# compass.net
KiCad netlist of a schematic drawn in EAGLE
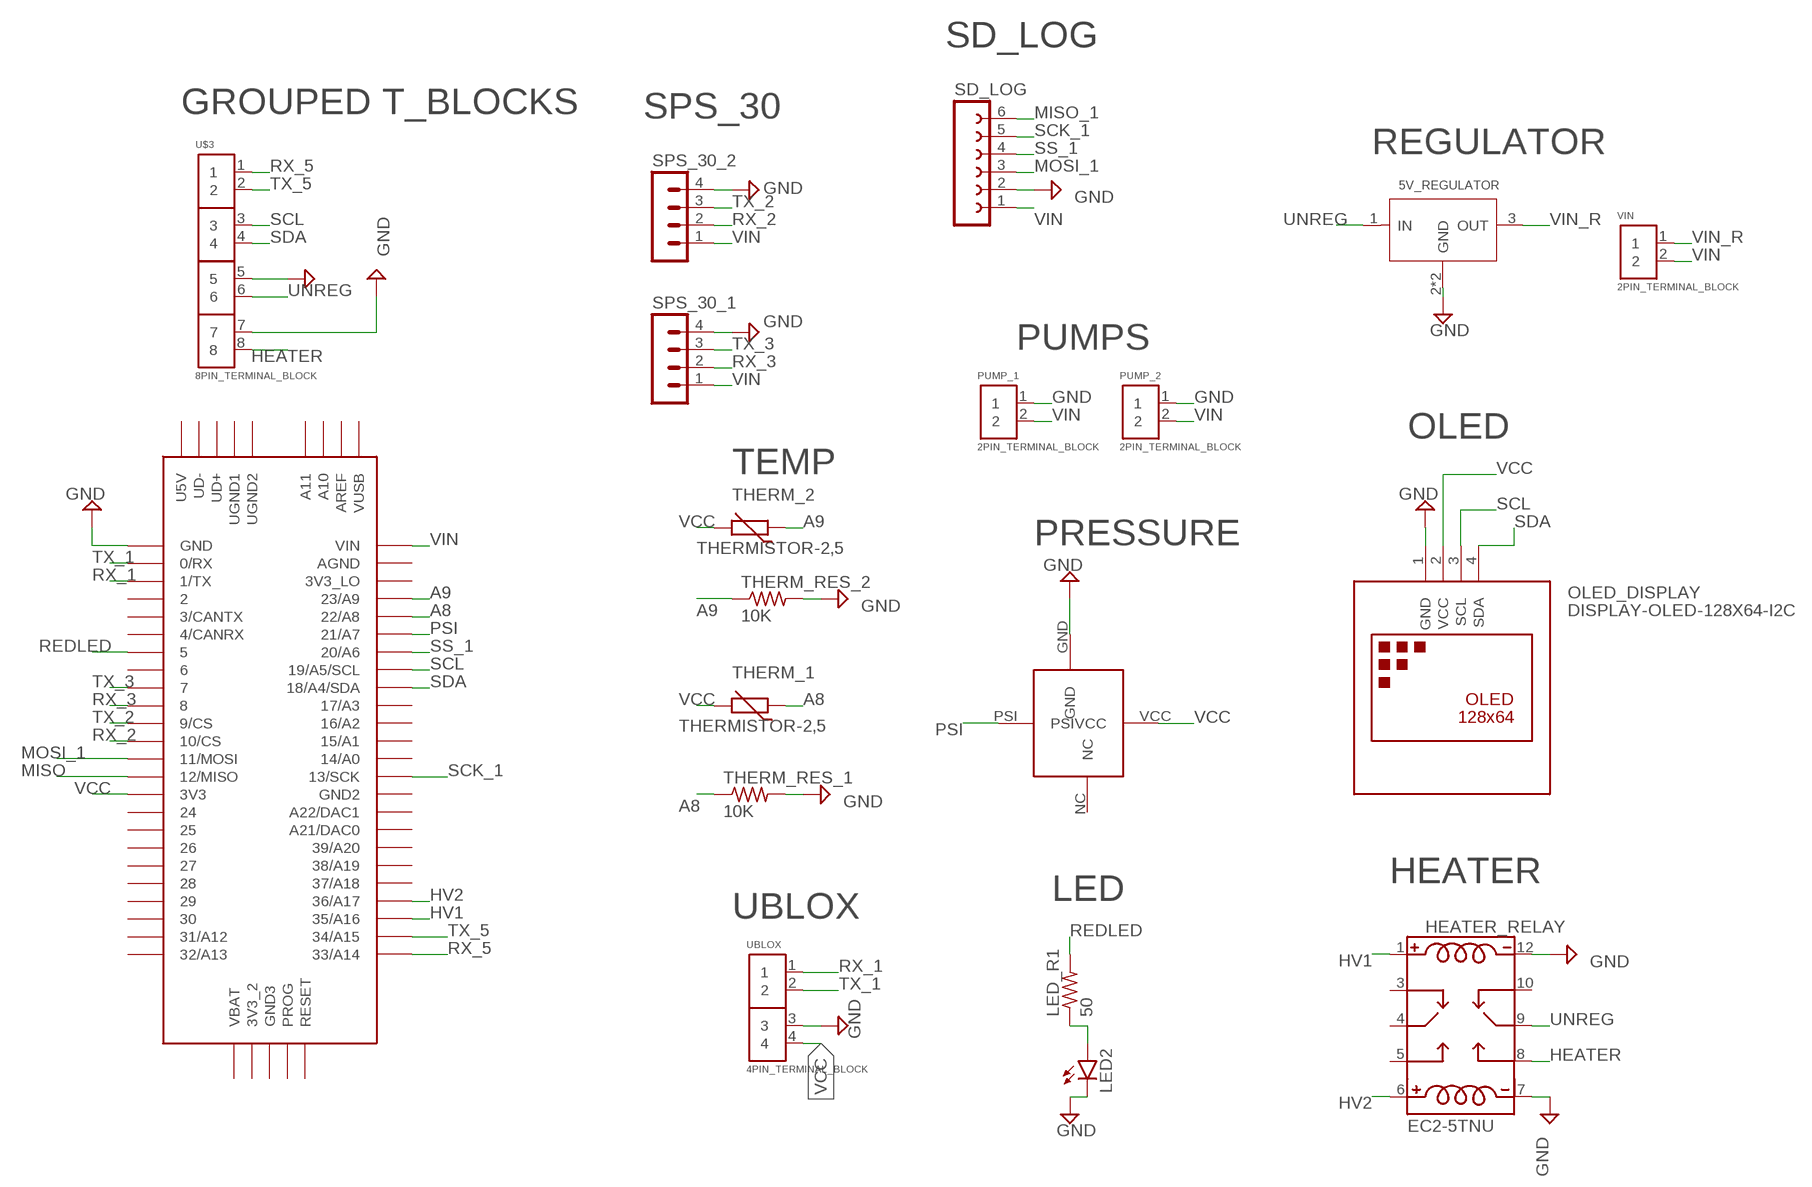
[diagram p0: schematic, sheet 1]

(export (version "E")
  (design (tool "Eeschema 10.0.6"))
  (components
    (comp (ref "5V_REGULATOR")
      (value "PMIC-L7805CV-DG(TO-220)")
      (footprint "eagle-import:TO-220")
      (fields
        (field (name "DIGI-KEY_PART_NUMBER") "497-12404-ND")
        (field (name "MF") "STMicroelectronics")
        (field (name "MP") "L7805CV-DG")
      )
      (libsource (lib "eagle-import") (part "PMIC-L7805CV-DG(TO-220)"))
    )
    (comp (ref "HEATER_RELAY")
      (value "EC2-5TNU")
      (footprint "eagle-import:RELAY_EC2-5TNU")
      (fields (field (name "MF") "KEMET"))
      (libsource (lib "eagle-import") (part "EC2-5TNU"))
    )
    (comp (ref "LED2")
      (value "TLLR4400")
      (footprint "eagle-import:LED3MM")
      (fields (field (name "MF") "VISHAY SEMICONDUCTOR"))
      (libsource (lib "eagle-import") (part "TLLR4400"))
    )
    (comp (ref "LED_R1")
      (value "50")
      (footprint "eagle-import:0204_7")
      (libsource (lib "eagle-import") (part "resistor_348_R-US_0204/7"))
    )
    (comp (ref "OLED_DISPLAY")
      (value "DISPLAY-OLED-128X64-I2C")
      (footprint "eagle-import:DISPLAY-OLED-128X64-I2C")
      (libsource (lib "eagle-import") (part "DISPLAY-OLED-128X64-I2C"))
    )
    (comp (ref "PRESSURE_SENSOR")
      (value "SSCSANN015PAAA5")
      (footprint "eagle-import:SSCSANN015PAAA5")
      (libsource (lib "eagle-import") (part "SSCSANN015PAAA5"))
    )
    (comp (ref "PUMP_1")
      (value "2PIN_TERMINAL_BLOCK")
      (footprint "eagle-import:2PIN_TERMINAL_BLOCK")
      (fields
        (field (name "COMMENT") "282834-2")
        (field (name "DIGI-KEY_PART_NUMBER") "A98333-ND")
        (field (name "MF") "TE Connectivity")
      )
      (libsource (lib "eagle-import") (part "2PIN_TERMINAL_BLOCK"))
    )
    (comp (ref "PUMP_2")
      (value "2PIN_TERMINAL_BLOCK")
      (footprint "eagle-import:2PIN_TERMINAL_BLOCK")
      (fields
        (field (name "COMMENT") "282834-2")
        (field (name "DIGI-KEY_PART_NUMBER") "A98333-ND")
        (field (name "MF") "TE Connectivity")
      )
      (libsource (lib "eagle-import") (part "2PIN_TERMINAL_BLOCK"))
    )
    (comp (ref "SD_LOG")
      (value "FE06-1")
      (footprint "eagle-import:FE06")
      (libsource (lib "eagle-import") (part "FE06-1"))
    )
    (comp (ref "SPS_30_1")
      (value "MA04-1")
      (footprint "eagle-import:MA04-1")
      (libsource (lib "eagle-import") (part "MA04-1"))
    )
    (comp (ref "SPS_30_2")
      (value "MA04-1")
      (footprint "eagle-import:MA04-1")
      (libsource (lib "eagle-import") (part "MA04-1"))
    )
    (comp (ref "THERM_1")
      (value "THERMISTOR-2,5")
      (footprint "eagle-import:RS-2,5")
      (libsource (lib "eagle-import") (part "THERMISTOR-2,5"))
    )
    (comp (ref "THERM_2")
      (value "THERMISTOR-2,5")
      (footprint "eagle-import:RS-2,5")
      (libsource (lib "eagle-import") (part "THERMISTOR-2,5"))
    )
    (comp (ref "THERM_RES_1")
      (value "10K")
      (footprint "eagle-import:0204_7")
      (libsource (lib "eagle-import") (part "R-US_0204/7"))
    )
    (comp (ref "THERM_RES_2")
      (value "10K")
      (footprint "eagle-import:0204_7")
      (libsource (lib "eagle-import") (part "R-US_0204/7"))
    )
    (comp (ref "U$1")
      (value "TEENSY_3.5/3.6")
      (footprint "eagle-import:TEENSY_3.5_3.6")
      (libsource (lib "eagle-import") (part "TEENSY_3.5/3.6"))
    )
    (comp (ref "U$3")
      (value "8PIN_TERMINAL_BLOCK")
      (footprint "eagle-import:8PIN_TERMINAL_BLOCK")
      (libsource (lib "eagle-import") (part "8PIN_TERMINAL_BLOCK"))
    )
    (comp (ref "UBLOX")
      (value "4PIN_TERMINAL_BLOCK")
      (footprint "eagle-import:4PIN_TERMINAL_BLOCK")
      (libsource (lib "eagle-import") (part "4PIN_TERMINAL_BLOCK"))
    )
    (comp (ref "VIN")
      (value "2PIN_TERMINAL_BLOCK")
      (footprint "eagle-import:2PIN_TERMINAL_BLOCK")
      (fields
        (field (name "COMMENT") "282834-2")
        (field (name "DIGI-KEY_PART_NUMBER") "A98333-ND")
        (field (name "MF") "TE Connectivity")
      )
      (libsource (lib "eagle-import") (part "2PIN_TERMINAL_BLOCK"))
    )
  )
  (nets
    (net (code "1") (name "/A8") (class "Default")
      (node (ref "THERM_1") (pin "1") (pinfunction "1_1") (pintype "passive"))
      (node (ref "THERM_RES_1") (pin "1") (pinfunction "1_1") (pintype "passive"))
      (node (ref "U$1") (pin "22/A8") (pinfunction "22/A8_22/A8") (pintype "bidirectional"))
    )
    (net (code "2") (name "/A9") (class "Default")
      (node (ref "THERM_2") (pin "1") (pinfunction "1_1") (pintype "passive"))
      (node (ref "THERM_RES_2") (pin "1") (pinfunction "1_1") (pintype "passive"))
      (node (ref "U$1") (pin "23/A9") (pinfunction "23/A9_23/A9") (pintype "bidirectional"))
    )
    (net (code "3") (name "/HEATER") (class "Default")
      (node (ref "HEATER_RELAY") (pin "8") (pinfunction "NO_8") (pintype "passive"))
      (node (ref "U$3") (pin "8") (pinfunction "8_8") (pintype "passive"))
    )
    (net (code "4") (name "/HV1") (class "Default")
      (node (ref "HEATER_RELAY") (pin "1") (pinfunction "C1_1") (pintype "passive"))
      (node (ref "U$1") (pin "35/A16") (pinfunction "35/A16_35/A16") (pintype "bidirectional"))
    )
    (net (code "5") (name "/HV2") (class "Default")
      (node (ref "HEATER_RELAY") (pin "6") (pinfunction "C3_6") (pintype "passive"))
      (node (ref "U$1") (pin "36/A17") (pinfunction "36/A17_36/A17") (pintype "bidirectional"))
    )
    (net (code "6") (name "/MISO") (class "Default")
      (node (ref "U$1") (pin "12/MISO") (pinfunction "12/MISO_12/MISO") (pintype "bidirectional"))
    )
    (net (code "7") (name "/MISO_1") (class "Default")
      (node (ref "SD_LOG") (pin "6") (pinfunction "6_6") (pintype "passive"))
    )
    (net (code "8") (name "/MOSI_1") (class "Default")
      (node (ref "SD_LOG") (pin "3") (pinfunction "3_3") (pintype "passive"))
      (node (ref "U$1") (pin "11/MOSI") (pinfunction "11/MOSI_11/MOSI") (pintype "bidirectional"))
    )
    (net (code "9") (name "/PSI") (class "Default")
      (node (ref "PRESSURE_SENSOR") (pin "PSI") (pinfunction "PSI_PSI") (pintype "bidirectional"))
      (node (ref "U$1") (pin "21/A7") (pinfunction "21/A7_21/A7") (pintype "bidirectional"))
    )
    (net (code "10") (name "/REDLED") (class "Default")
      (node (ref "LED_R1") (pin "2") (pinfunction "2_2") (pintype "passive"))
      (node (ref "U$1") (pin "5") (pinfunction "5_5") (pintype "bidirectional"))
    )
    (net (code "11") (name "/RX_1") (class "Default")
      (node (ref "U$1") (pin "1/TX") (pinfunction "1/TX_1/TX") (pintype "bidirectional"))
      (node (ref "UBLOX") (pin "1") (pinfunction "1_1") (pintype "passive"))
    )
    (net (code "12") (name "/RX_2") (class "Default")
      (node (ref "SPS_30_2") (pin "2") (pinfunction "2_2") (pintype "passive"))
      (node (ref "U$1") (pin "10/CS") (pinfunction "10/CS_10/CS") (pintype "bidirectional"))
    )
    (net (code "13") (name "/RX_3") (class "Default")
      (node (ref "SPS_30_1") (pin "2") (pinfunction "2_2") (pintype "passive"))
      (node (ref "U$1") (pin "8") (pinfunction "8_8") (pintype "bidirectional"))
    )
    (net (code "14") (name "/RX_5") (class "Default")
      (node (ref "U$1") (pin "33/A14") (pinfunction "33/A14_33/A14") (pintype "bidirectional"))
      (node (ref "U$3") (pin "1") (pinfunction "1_1") (pintype "passive"))
    )
    (net (code "15") (name "/SCK_1") (class "Default")
      (node (ref "SD_LOG") (pin "5") (pinfunction "5_5") (pintype "passive"))
      (node (ref "U$1") (pin "13/SCK") (pinfunction "13/SCK_13/SCK") (pintype "bidirectional"))
    )
    (net (code "16") (name "/SCL") (class "Default")
      (node (ref "OLED_DISPLAY") (pin "3") (pinfunction "SCL_3") (pintype "bidirectional"))
      (node (ref "U$1") (pin "19/A5/SCL") (pinfunction "19/A5/SCL_19/A5/SCL") (pintype "bidirectional"))
      (node (ref "U$3") (pin "3") (pinfunction "3_3") (pintype "passive"))
    )
    (net (code "17") (name "/SDA") (class "Default")
      (node (ref "OLED_DISPLAY") (pin "4") (pinfunction "SDA_4") (pintype "bidirectional"))
      (node (ref "U$1") (pin "18/A4/SDA") (pinfunction "18/A4/SDA_18/A4/SDA") (pintype "bidirectional"))
      (node (ref "U$3") (pin "4") (pinfunction "4_4") (pintype "passive"))
    )
    (net (code "18") (name "/SS_1") (class "Default")
      (node (ref "SD_LOG") (pin "4") (pinfunction "4_4") (pintype "passive"))
      (node (ref "U$1") (pin "20/A6") (pinfunction "20/A6_20/A6") (pintype "bidirectional"))
    )
    (net (code "19") (name "/TX_1") (class "Default")
      (node (ref "U$1") (pin "0/RX") (pinfunction "0/RX_0/RX") (pintype "bidirectional"))
      (node (ref "UBLOX") (pin "2") (pinfunction "2_2") (pintype "passive"))
    )
    (net (code "20") (name "/TX_2") (class "Default")
      (node (ref "SPS_30_2") (pin "3") (pinfunction "3_3") (pintype "passive"))
      (node (ref "U$1") (pin "9/CS") (pinfunction "9/CS_9/CS") (pintype "bidirectional"))
    )
    (net (code "21") (name "/TX_3") (class "Default")
      (node (ref "SPS_30_1") (pin "3") (pinfunction "3_3") (pintype "passive"))
      (node (ref "U$1") (pin "7") (pinfunction "7_7") (pintype "bidirectional"))
    )
    (net (code "22") (name "/TX_5") (class "Default")
      (node (ref "U$1") (pin "34/A15") (pinfunction "34/A15_34/A15") (pintype "bidirectional"))
      (node (ref "U$3") (pin "2") (pinfunction "2_2") (pintype "passive"))
    )
    (net (code "23") (name "/UNREG") (class "Default")
      (node (ref "5V_REGULATOR") (pin "1") (pinfunction "IN_1") (pintype "bidirectional"))
      (node (ref "HEATER_RELAY") (pin "9") (pinfunction "M_9") (pintype "passive"))
      (node (ref "U$3") (pin "6") (pinfunction "6_6") (pintype "passive"))
    )
    (net (code "24") (name "/VIN") (class "Default")
      (node (ref "PUMP_1") (pin "2") (pinfunction "2_2") (pintype "passive"))
      (node (ref "PUMP_2") (pin "2") (pinfunction "2_2") (pintype "passive"))
      (node (ref "SD_LOG") (pin "1") (pinfunction "1_1") (pintype "passive"))
      (node (ref "SPS_30_1") (pin "1") (pinfunction "1_1") (pintype "passive"))
      (node (ref "SPS_30_2") (pin "1") (pinfunction "1_1") (pintype "passive"))
      (node (ref "U$1") (pin "VIN") (pinfunction "VIN_VIN") (pintype "bidirectional"))
      (node (ref "VIN") (pin "2") (pinfunction "2_2") (pintype "passive"))
    )
    (net (code "25") (name "/VIN_R") (class "Default")
      (node (ref "5V_REGULATOR") (pin "3") (pinfunction "OUT_3") (pintype "bidirectional"))
      (node (ref "VIN") (pin "1") (pinfunction "1_1") (pintype "passive"))
    )
    (net (code "26") (name "GND") (class "Default")
      (node (ref "5V_REGULATOR") (pin "2") (pinfunction "GND_2") (pintype "bidirectional"))
      (node (ref "5V_REGULATOR") (pin "HEAT") (pinfunction "GND_HEAT") (pintype "bidirectional"))
      (node (ref "HEATER_RELAY") (pin "12") (pinfunction "C2_12") (pintype "passive"))
      (node (ref "HEATER_RELAY") (pin "7") (pinfunction "C4_7") (pintype "passive"))
      (node (ref "LED2") (pin "K") (pinfunction "C_K") (pintype "passive"))
      (node (ref "OLED_DISPLAY") (pin "1") (pinfunction "GND_1") (pintype "power_in"))
      (node (ref "PRESSURE_SENSOR") (pin "GND") (pinfunction "GND_GND") (pintype "bidirectional"))
      (node (ref "PUMP_1") (pin "1") (pinfunction "1_1") (pintype "passive"))
      (node (ref "PUMP_2") (pin "1") (pinfunction "1_1") (pintype "passive"))
      (node (ref "SD_LOG") (pin "2") (pinfunction "2_2") (pintype "passive"))
      (node (ref "SPS_30_1") (pin "4") (pinfunction "4_4") (pintype "passive"))
      (node (ref "SPS_30_2") (pin "4") (pinfunction "4_4") (pintype "passive"))
      (node (ref "THERM_RES_1") (pin "2") (pinfunction "2_2") (pintype "passive"))
      (node (ref "THERM_RES_2") (pin "2") (pinfunction "2_2") (pintype "passive"))
      (node (ref "U$1") (pin "GND") (pinfunction "GND_GND") (pintype "bidirectional"))
      (node (ref "U$3") (pin "5") (pinfunction "5_5") (pintype "passive"))
      (node (ref "U$3") (pin "7") (pinfunction "7_7") (pintype "passive"))
      (node (ref "UBLOX") (pin "3") (pinfunction "3_3") (pintype "passive"))
    )
    (net (code "27") (name "Net-(LED2-PadA)") (class "Default")
      (node (ref "LED2") (pin "A") (pinfunction "A_A") (pintype "passive"))
      (node (ref "LED_R1") (pin "1") (pinfunction "1_1") (pintype "passive"))
    )
    (net (code "28") (name "VCC") (class "Default")
      (node (ref "OLED_DISPLAY") (pin "2") (pinfunction "VCC_2") (pintype "power_in"))
      (node (ref "PRESSURE_SENSOR") (pin "VCC") (pinfunction "VCC_VCC") (pintype "bidirectional"))
      (node (ref "THERM_1") (pin "2") (pinfunction "2_2") (pintype "passive"))
      (node (ref "THERM_2") (pin "2") (pinfunction "2_2") (pintype "passive"))
      (node (ref "U$1") (pin "3V3") (pinfunction "3V3_3V3") (pintype "bidirectional"))
      (node (ref "UBLOX") (pin "4") (pinfunction "4_4") (pintype "passive"))
    )
    (net (code "29") (name "unconnected-(HEATER_RELAY-M1-Pad4)") (class "Default")
      (node (ref "HEATER_RELAY") (pin "4") (pinfunction "M1_4") (pintype "passive"))
    )
    (net (code "30") (name "unconnected-(HEATER_RELAY-NC-Pad10)") (class "Default")
      (node (ref "HEATER_RELAY") (pin "10") (pinfunction "NC_10") (pintype "passive"))
    )
    (net (code "31") (name "unconnected-(HEATER_RELAY-NC1-Pad3)") (class "Default")
      (node (ref "HEATER_RELAY") (pin "3") (pinfunction "NC1_3") (pintype "passive"))
    )
    (net (code "32") (name "unconnected-(HEATER_RELAY-NO1-Pad5)") (class "Default")
      (node (ref "HEATER_RELAY") (pin "5") (pinfunction "NO1_5") (pintype "passive"))
    )
    (net (code "33") (name "unconnected-(PRESSURE_SENSOR-PadNC)") (class "Default")
      (node (ref "PRESSURE_SENSOR") (pin "NC") (pinfunction "NC_NC") (pintype "bidirectional"))
    )
    (net (code "34") (name "unconnected-(U$1-A21{slash}DAC0-Pad21{slash}DAC0)") (class "Default")
      (node (ref "U$1") (pin "21/DAC0") (pinfunction "A21/DAC0_21/DAC0") (pintype "bidirectional"))
    )
    (net (code "35") (name "unconnected-(U$1-Pad2)") (class "Default")
      (node (ref "U$1") (pin "2") (pinfunction "2_2") (pintype "bidirectional"))
    )
    (net (code "36") (name "unconnected-(U$1-Pad3V3_2)") (class "Default")
      (node (ref "U$1") (pin "3V3_2") (pinfunction "3V3_2_3V3_2") (pintype "bidirectional"))
    )
    (net (code "37") (name "unconnected-(U$1-Pad3V3_LO)") (class "Default")
      (node (ref "U$1") (pin "3V3_LO") (pinfunction "3V3_LO_3V3_LO") (pintype "bidirectional"))
    )
    (net (code "38") (name "unconnected-(U$1-Pad3{slash}CANTX)") (class "Default")
      (node (ref "U$1") (pin "3/CANTX") (pinfunction "3/CANTX_3/CANTX") (pintype "bidirectional"))
    )
    (net (code "39") (name "unconnected-(U$1-Pad4{slash}CANRX)") (class "Default")
      (node (ref "U$1") (pin "4/CANRX") (pinfunction "4/CANRX_4/CANRX") (pintype "bidirectional"))
    )
    (net (code "40") (name "unconnected-(U$1-Pad6)") (class "Default")
      (node (ref "U$1") (pin "6") (pinfunction "6_6") (pintype "bidirectional"))
    )
    (net (code "41") (name "unconnected-(U$1-Pad14{slash}A0)") (class "Default")
      (node (ref "U$1") (pin "14/A0") (pinfunction "14/A0_14/A0") (pintype "bidirectional"))
    )
    (net (code "42") (name "unconnected-(U$1-Pad15{slash}A1)") (class "Default")
      (node (ref "U$1") (pin "15/A1") (pinfunction "15/A1_15/A1") (pintype "bidirectional"))
    )
    (net (code "43") (name "unconnected-(U$1-Pad16{slash}A2)") (class "Default")
      (node (ref "U$1") (pin "16/A2") (pinfunction "16/A2_16/A2") (pintype "bidirectional"))
    )
    (net (code "44") (name "unconnected-(U$1-Pad17{slash}A3)") (class "Default")
      (node (ref "U$1") (pin "17/A3") (pinfunction "17/A3_17/A3") (pintype "bidirectional"))
    )
    (net (code "45") (name "unconnected-(U$1-Pad24)") (class "Default")
      (node (ref "U$1") (pin "24") (pinfunction "24_24") (pintype "bidirectional"))
    )
    (net (code "46") (name "unconnected-(U$1-Pad25)") (class "Default")
      (node (ref "U$1") (pin "25") (pinfunction "25_25") (pintype "bidirectional"))
    )
    (net (code "47") (name "unconnected-(U$1-Pad26)") (class "Default")
      (node (ref "U$1") (pin "26") (pinfunction "26_26") (pintype "bidirectional"))
    )
    (net (code "48") (name "unconnected-(U$1-Pad27)") (class "Default")
      (node (ref "U$1") (pin "27") (pinfunction "27_27") (pintype "bidirectional"))
    )
    (net (code "49") (name "unconnected-(U$1-Pad28)") (class "Default")
      (node (ref "U$1") (pin "28") (pinfunction "28_28") (pintype "bidirectional"))
    )
    (net (code "50") (name "unconnected-(U$1-Pad29)") (class "Default")
      (node (ref "U$1") (pin "29") (pinfunction "29_29") (pintype "bidirectional"))
    )
    (net (code "51") (name "unconnected-(U$1-Pad30)") (class "Default")
      (node (ref "U$1") (pin "30") (pinfunction "30_30") (pintype "bidirectional"))
    )
    (net (code "52") (name "unconnected-(U$1-Pad31{slash}A12)") (class "Default")
      (node (ref "U$1") (pin "31/A12") (pinfunction "31/A12_31/A12") (pintype "bidirectional"))
    )
    (net (code "53") (name "unconnected-(U$1-Pad32{slash}A13)") (class "Default")
      (node (ref "U$1") (pin "32/A13") (pinfunction "32/A13_32/A13") (pintype "bidirectional"))
    )
    (net (code "54") (name "unconnected-(U$1-Pad37{slash}A18)") (class "Default")
      (node (ref "U$1") (pin "37/A18") (pinfunction "37/A18_37/A18") (pintype "bidirectional"))
    )
    (net (code "55") (name "unconnected-(U$1-Pad38{slash}A19)") (class "Default")
      (node (ref "U$1") (pin "38/A19") (pinfunction "38/A19_38/A19") (pintype "bidirectional"))
    )
    (net (code "56") (name "unconnected-(U$1-Pad39{slash}A20)") (class "Default")
      (node (ref "U$1") (pin "39/A20") (pinfunction "39/A20_39/A20") (pintype "bidirectional"))
    )
    (net (code "57") (name "unconnected-(U$1-PadA10)") (class "Default")
      (node (ref "U$1") (pin "A10") (pinfunction "A10_A10") (pintype "bidirectional"))
    )
    (net (code "58") (name "unconnected-(U$1-PadA11)") (class "Default")
      (node (ref "U$1") (pin "A11") (pinfunction "A11_A11") (pintype "bidirectional"))
    )
    (net (code "59") (name "unconnected-(U$1-PadA22{slash}DAC1)") (class "Default")
      (node (ref "U$1") (pin "A22/DAC1") (pinfunction "A22/DAC1_A22/DAC1") (pintype "bidirectional"))
    )
    (net (code "60") (name "unconnected-(U$1-PadAGND)") (class "Default")
      (node (ref "U$1") (pin "AGND") (pinfunction "AGND_AGND") (pintype "bidirectional"))
    )
    (net (code "61") (name "unconnected-(U$1-PadAREF)") (class "Default")
      (node (ref "U$1") (pin "AREF") (pinfunction "AREF_AREF") (pintype "bidirectional"))
    )
    (net (code "62") (name "unconnected-(U$1-PadGND2)") (class "Default")
      (node (ref "U$1") (pin "GND2") (pinfunction "GND2_GND2") (pintype "bidirectional"))
    )
    (net (code "63") (name "unconnected-(U$1-PadGND3)") (class "Default")
      (node (ref "U$1") (pin "GND3") (pinfunction "GND3_GND3") (pintype "bidirectional"))
    )
    (net (code "64") (name "unconnected-(U$1-PadPROG)") (class "Default")
      (node (ref "U$1") (pin "PROG") (pinfunction "PROG_PROG") (pintype "bidirectional"))
    )
    (net (code "65") (name "unconnected-(U$1-PadRESET)") (class "Default")
      (node (ref "U$1") (pin "RESET") (pinfunction "RESET_RESET") (pintype "bidirectional"))
    )
    (net (code "66") (name "unconnected-(U$1-PadU5V)") (class "Default")
      (node (ref "U$1") (pin "U5V") (pinfunction "U5V_U5V") (pintype "bidirectional"))
    )
    (net (code "67") (name "unconnected-(U$1-PadUD+)") (class "Default")
      (node (ref "U$1") (pin "UD+") (pinfunction "UD+_UD+") (pintype "bidirectional"))
    )
    (net (code "68") (name "unconnected-(U$1-PadUD-)") (class "Default")
      (node (ref "U$1") (pin "UD-") (pinfunction "UD-_UD-") (pintype "bidirectional"))
    )
    (net (code "69") (name "unconnected-(U$1-PadUGND1)") (class "Default")
      (node (ref "U$1") (pin "UGND1") (pinfunction "UGND1_UGND1") (pintype "bidirectional"))
    )
    (net (code "70") (name "unconnected-(U$1-PadUGND2)") (class "Default")
      (node (ref "U$1") (pin "UGND2") (pinfunction "UGND2_UGND2") (pintype "bidirectional"))
    )
    (net (code "71") (name "unconnected-(U$1-PadVBAT)") (class "Default")
      (node (ref "U$1") (pin "VBAT") (pinfunction "VBAT_VBAT") (pintype "bidirectional"))
    )
    (net (code "72") (name "unconnected-(U$1-PadVUSB)") (class "Default")
      (node (ref "U$1") (pin "VUSB") (pinfunction "VUSB_VUSB") (pintype "bidirectional"))
    )
  )
)
